# Gate_Control.net
KiCad netlist of a schematic drawn in Altium Designer
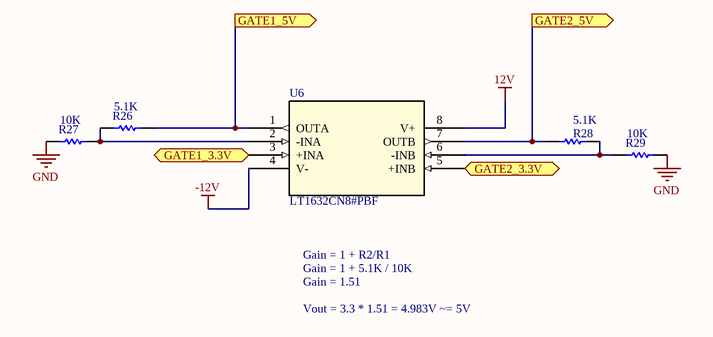
[diagram p0: Gate_Control.SchDoc]

(export (version "E")
  (design (tool "Eeschema 10.0.6"))
  (components
    (comp (ref "R26")
      (value "5.1K")
      (footprint "AXIAL-0.3")
      (description "Resistor")
      (fields (field (name "Comment") "Res1") (field (name "PUBLISHER") "Altium Limited"))
      (libsource (lib "Miscellaneous Devices") (part "Res1"))
    )
    (comp (ref "R27")
      (value "10K")
      (footprint "AXIAL-0.3")
      (description "Resistor")
      (fields (field (name "Comment") "Res1") (field (name "PUBLISHER") "Altium Limited"))
      (libsource (lib "Miscellaneous Devices") (part "Res1"))
    )
    (comp (ref "R28")
      (value "5.1K")
      (footprint "AXIAL-0.3")
      (description "Resistor")
      (fields (field (name "Comment") "Res1") (field (name "PUBLISHER") "Altium Limited"))
      (libsource (lib "Miscellaneous Devices") (part "Res1"))
    )
    (comp (ref "R29")
      (value "10K")
      (footprint "AXIAL-0.3")
      (description "Resistor")
      (fields (field (name "Comment") "Res1") (field (name "PUBLISHER") "Altium Limited"))
      (libsource (lib "Miscellaneous Devices") (part "Res1"))
    )
    (comp (ref "U6")
      (value "LT1632CN8#PBF")
      (footprint "PDIP-8_N")
      (description "Imported")
      (fields
        (field (name "DIGIKEYPARTNUMBER") "LT1632CN8-ND")
        (field (name "COPYRIGHT") "Copyright (C) 2015 Accelerated Designs. All rights reserved")
      )
      (libsource (lib "lt1632") (part "LT1632CN8#PBF"))
    )
  )
  (nets
    (net (code "1") (name "-12V") (class "Default")
      (node (ref "U6") (pin "4") (pinfunction "V-_4") (pintype "power_in"))
    )
    (net (code "2") (name "/GATE1_3.3V") (class "Default")
      (node (ref "U6") (pin "3") (pinfunction "+INA_3") (pintype "input"))
    )
    (net (code "3") (name "/GATE1_5V") (class "Default")
      (node (ref "R26") (pin "2") (pinfunction "2_2") (pintype "passive"))
      (node (ref "U6") (pin "1") (pinfunction "OUTA_1") (pintype "output"))
    )
    (net (code "4") (name "/GATE2_3.3V") (class "Default")
      (node (ref "U6") (pin "5") (pinfunction "+INB_5") (pintype "input"))
    )
    (net (code "5") (name "/GATE2_5V") (class "Default")
      (node (ref "R28") (pin "1") (pinfunction "1_1") (pintype "passive"))
      (node (ref "U6") (pin "7") (pinfunction "OUTB_7") (pintype "output"))
    )
    (net (code "6") (name "12V") (class "Default")
      (node (ref "U6") (pin "8") (pinfunction "V+_8") (pintype "power_in"))
    )
    (net (code "7") (name "GND") (class "Default")
      (node (ref "R27") (pin "1") (pinfunction "1_1") (pintype "passive"))
      (node (ref "R29") (pin "2") (pinfunction "2_2") (pintype "passive"))
    )
    (net (code "8") (name "Net-(U6--INA)") (class "Default")
      (node (ref "R26") (pin "1") (pinfunction "1_1") (pintype "passive"))
      (node (ref "R27") (pin "2") (pinfunction "2_2") (pintype "passive"))
      (node (ref "U6") (pin "2") (pinfunction "-INA_2") (pintype "input"))
    )
    (net (code "9") (name "Net-(U6--INB)") (class "Default")
      (node (ref "R28") (pin "2") (pinfunction "2_2") (pintype "passive"))
      (node (ref "R29") (pin "1") (pinfunction "1_1") (pintype "passive"))
      (node (ref "U6") (pin "6") (pinfunction "-INB_6") (pintype "input"))
    )
  )
)
